# 03-8A34004_DPLL-1.net
KiCad netlist of a schematic drawn in Altium Designer
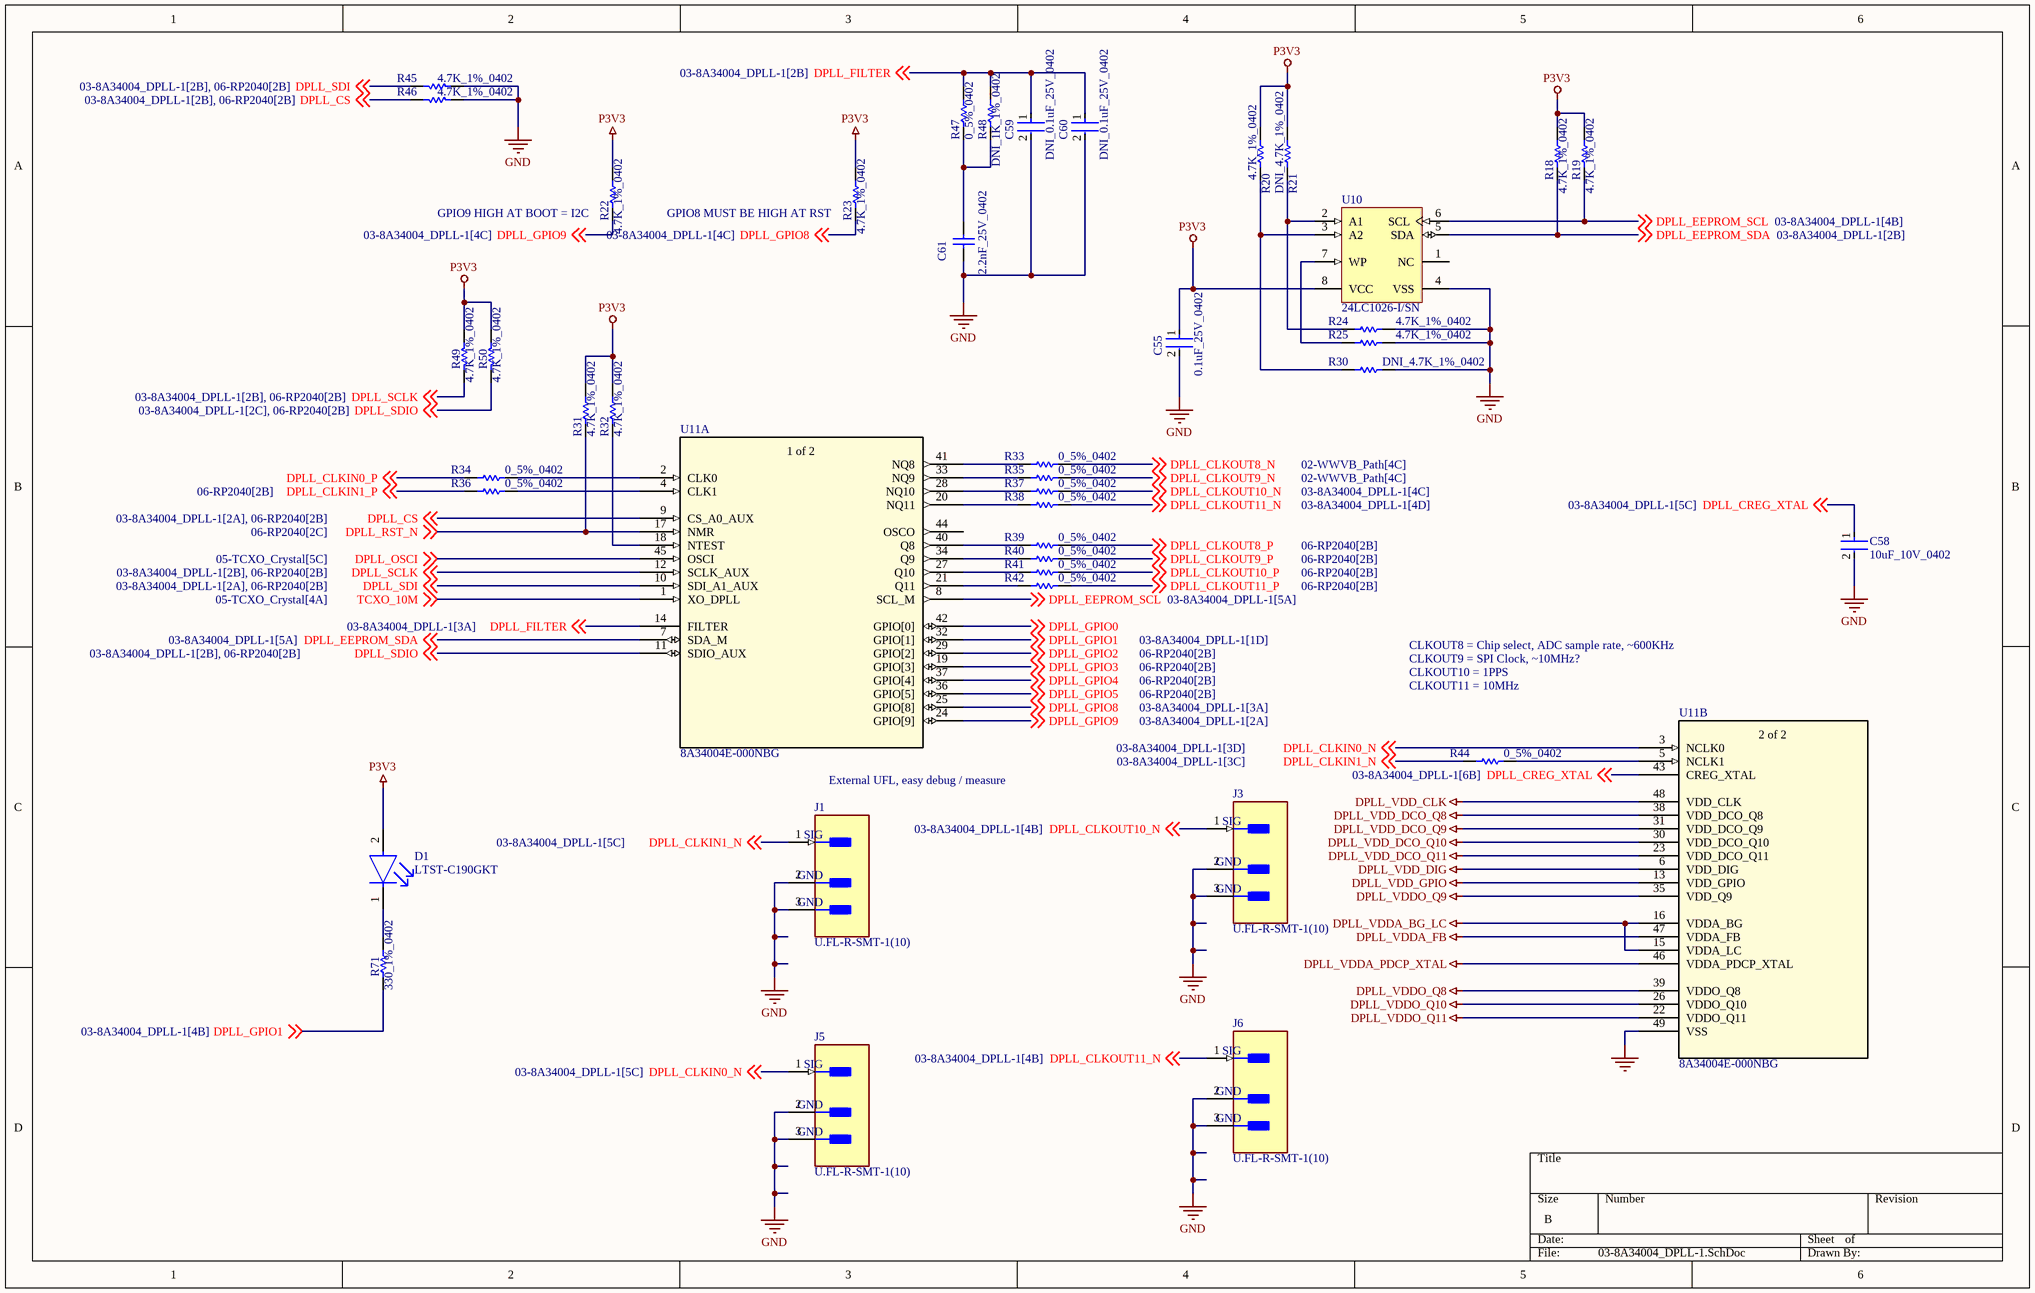
[diagram p0: 03-8A34004_DPLL-1.SchDoc]

(export (version "E")
  (design (tool "Eeschema 10.0.6"))
  (components
    (comp (ref "C55")
      (value "0.1uF_25V_0402")
      (footprint "FP-0402-L_1_0_1-W_0_5_0_1-IPC_C")
      (description "General Purpose Ceramic Capacitor, 0402, 100nF, 10%, X7R, 15%, 25V")
      (fields (field (name "VOLTAGE") "25V") (field (name "TOLERANCE") "10%"))
      (libsource (lib "Altium Content Vault") (part "b4654b650e69147ec39a6b967a45e02"))
    )
    (comp (ref "C58")
      (value "10uF_10V_0402")
      (footprint "FP-CL05A106MP5NUNC-MFG")
      (description "CAP CER 10UF 10V X5R 0402")
      (fields
        (field (name "OCTOPART") "https://octopart.com/cl05a106mp5nunc-samsung-22457395")
        (field (name "TOLERANCE") "20%")
      )
      (libsource (lib "Altium Content Vault") (part "b4654b650e69147ec39a6b967a45e02"))
    )
    (comp (ref "C59")
      (value "DNI_0.1uF_25V_0402")
      (footprint "FP-0402-L_1_0_1-W_0_5_0_1-IPC_C")
      (description "General Purpose Ceramic Capacitor, 0402, 100nF, 10%, X7R, 15%, 25V")
      (fields (field (name "VOLTAGE") "25V") (field (name "TOLERANCE") "10%"))
      (libsource (lib "Altium Content Vault") (part "b4654b650e69147ec39a6b967a45e02"))
    )
    (comp (ref "C60")
      (value "DNI_0.1uF_25V_0402")
      (footprint "FP-0402-L_1_0_1-W_0_5_0_1-IPC_C")
      (description "General Purpose Ceramic Capacitor, 0402, 100nF, 10%, X7R, 15%, 25V")
      (fields (field (name "VOLTAGE") "25V") (field (name "TOLERANCE") "10%"))
      (libsource (lib "Altium Content Vault") (part "b4654b650e69147ec39a6b967a45e02"))
    )
    (comp (ref "C61")
      (value "2.2nF_25V_0402")
      (footprint "CAPC1005X56X25LL10T15")
      (fields
        (field (name "MANUFACTURER") "AVX Interconnect / Elco")
        (field (name "PART NUMBER") "04025C222JAT2A")
      )
      (libsource (lib "Altium Content Vault") (part "CAP"))
    )
    (comp (ref "D1")
      (value "LTST-C190GKT")
      (footprint "FP-LTST-C190GKT-MFG")
      (description "LED GREEN CLEAR CHIP SMD")
      (fields (field (name "VOLTAGE") "2V"))
      (libsource (lib "Altium Content Vault") (part "8706943c75ba83719d021d2fdc84c58"))
    )
    (comp (ref "J1")
      (value "U.FL-R-SMT-1(10)")
      (footprint "FP-U_FL-R-SMT-1_10-MFG")
      (description "CONN U.FL RCPT STR 50 OHM SMD")
      (libsource (lib "Altium Content Vault") (part "7158abf7d987fa84906f6fb0d115710"))
    )
    (comp (ref "J3")
      (value "U.FL-R-SMT-1(10)")
      (footprint "FP-U_FL-R-SMT-1_10-MFG")
      (description "CONN U.FL RCPT STR 50 OHM SMD")
      (libsource (lib "Altium Content Vault") (part "7158abf7d987fa84906f6fb0d115710"))
    )
    (comp (ref "J5")
      (value "U.FL-R-SMT-1(10)")
      (footprint "FP-U_FL-R-SMT-1_10-MFG")
      (description "CONN U.FL RCPT STR 50 OHM SMD")
      (libsource (lib "Altium Content Vault") (part "7158abf7d987fa84906f6fb0d115710"))
    )
    (comp (ref "J6")
      (value "U.FL-R-SMT-1(10)")
      (footprint "FP-U_FL-R-SMT-1_10-MFG")
      (description "CONN U.FL RCPT STR 50 OHM SMD")
      (libsource (lib "Altium Content Vault") (part "7158abf7d987fa84906f6fb0d115710"))
    )
    (comp (ref "R18")
      (value "4.7K_1%_0402")
      (footprint "RESC1005X40X25NL10T10")
      (fields (field (name "MANUFACTURER") "Bourns") (field (name "PART NUMBER") "CR0402-FX-4701GLF"))
      (libsource (lib "Altium Content Vault") (part "RES"))
    )
    (comp (ref "R19")
      (value "4.7K_1%_0402")
      (footprint "RESC1005X40X25NL10T10")
      (fields (field (name "MANUFACTURER") "Bourns") (field (name "PART NUMBER") "CR0402-FX-4701GLF"))
      (libsource (lib "Altium Content Vault") (part "RES"))
    )
    (comp (ref "R20")
      (value "4.7K_1%_0402")
      (footprint "RESC1005X40X25NL10T10")
      (fields (field (name "MANUFACTURER") "Bourns") (field (name "PART NUMBER") "CR0402-FX-4701GLF"))
      (libsource (lib "Altium Content Vault") (part "RES"))
    )
    (comp (ref "R21")
      (value "DNI_4.7K_1%_0402")
      (footprint "RESC1005X40X25NL10T10")
      (fields (field (name "MANUFACTURER") "Bourns") (field (name "PART NUMBER") "CR0402-FX-4701GLF"))
      (libsource (lib "Altium Content Vault") (part "RES"))
    )
    (comp (ref "R22")
      (value "4.7K_1%_0402")
      (footprint "RESC1005X40X25NL10T10")
      (fields (field (name "MANUFACTURER") "Bourns") (field (name "PART NUMBER") "CR0402-FX-4701GLF"))
      (libsource (lib "Altium Content Vault") (part "RES"))
    )
    (comp (ref "R23")
      (value "4.7K_1%_0402")
      (footprint "RESC1005X40X25NL10T10")
      (fields (field (name "MANUFACTURER") "Bourns") (field (name "PART NUMBER") "CR0402-FX-4701GLF"))
      (libsource (lib "Altium Content Vault") (part "RES"))
    )
    (comp (ref "R24")
      (value "4.7K_1%_0402")
      (footprint "RESC1005X40X25NL10T10")
      (fields (field (name "MANUFACTURER") "Bourns") (field (name "PART NUMBER") "CR0402-FX-4701GLF"))
      (libsource (lib "Altium Content Vault") (part "RES"))
    )
    (comp (ref "R25")
      (value "4.7K_1%_0402")
      (footprint "RESC1005X40X25NL10T10")
      (fields (field (name "MANUFACTURER") "Bourns") (field (name "PART NUMBER") "CR0402-FX-4701GLF"))
      (libsource (lib "Altium Content Vault") (part "RES"))
    )
    (comp (ref "R30")
      (value "DNI_4.7K_1%_0402")
      (footprint "RESC1005X40X25NL10T10")
      (fields (field (name "MANUFACTURER") "Bourns") (field (name "PART NUMBER") "CR0402-FX-4701GLF"))
      (libsource (lib "Altium Content Vault") (part "RES"))
    )
    (comp (ref "R31")
      (value "4.7K_1%_0402")
      (footprint "RESC1005X40X25NL10T10")
      (fields (field (name "MANUFACTURER") "Bourns") (field (name "PART NUMBER") "CR0402-FX-4701GLF"))
      (libsource (lib "Altium Content Vault") (part "RES"))
    )
    (comp (ref "R32")
      (value "4.7K_1%_0402")
      (footprint "RESC1005X40X25NL10T10")
      (fields (field (name "MANUFACTURER") "Bourns") (field (name "PART NUMBER") "CR0402-FX-4701GLF"))
      (libsource (lib "Altium Content Vault") (part "RES"))
    )
    (comp (ref "R33")
      (value "0_5%_0402")
      (footprint "RESC1005X40X25NL05T10")
      (fields (field (name "MANUFACTURER") "Panasonic") (field (name "PART NUMBER") "ERJ-U020R00X"))
      (libsource (lib "Altium Content Vault") (part "RES"))
    )
    (comp (ref "R34")
      (value "0_5%_0402")
      (footprint "RESC1005X40X25NL05T10")
      (fields (field (name "MANUFACTURER") "Panasonic") (field (name "PART NUMBER") "ERJ-U020R00X"))
      (libsource (lib "Altium Content Vault") (part "RES"))
    )
    (comp (ref "R35")
      (value "0_5%_0402")
      (footprint "RESC1005X40X25NL05T10")
      (fields (field (name "MANUFACTURER") "Panasonic") (field (name "PART NUMBER") "ERJ-U020R00X"))
      (libsource (lib "Altium Content Vault") (part "RES"))
    )
    (comp (ref "R36")
      (value "0_5%_0402")
      (footprint "RESC1005X40X25NL05T10")
      (fields (field (name "MANUFACTURER") "Panasonic") (field (name "PART NUMBER") "ERJ-U020R00X"))
      (libsource (lib "Altium Content Vault") (part "RES"))
    )
    (comp (ref "R37")
      (value "0_5%_0402")
      (footprint "RESC1005X40X25NL05T10")
      (fields (field (name "MANUFACTURER") "Panasonic") (field (name "PART NUMBER") "ERJ-U020R00X"))
      (libsource (lib "Altium Content Vault") (part "RES"))
    )
    (comp (ref "R38")
      (value "0_5%_0402")
      (footprint "RESC1005X40X25NL05T10")
      (fields (field (name "MANUFACTURER") "Panasonic") (field (name "PART NUMBER") "ERJ-U020R00X"))
      (libsource (lib "Altium Content Vault") (part "RES"))
    )
    (comp (ref "R39")
      (value "0_5%_0402")
      (footprint "RESC1005X40X25NL05T10")
      (fields (field (name "MANUFACTURER") "Panasonic") (field (name "PART NUMBER") "ERJ-U020R00X"))
      (libsource (lib "Altium Content Vault") (part "RES"))
    )
    (comp (ref "R40")
      (value "0_5%_0402")
      (footprint "RESC1005X40X25NL05T10")
      (fields (field (name "MANUFACTURER") "Panasonic") (field (name "PART NUMBER") "ERJ-U020R00X"))
      (libsource (lib "Altium Content Vault") (part "RES"))
    )
    (comp (ref "R41")
      (value "0_5%_0402")
      (footprint "RESC1005X40X25NL05T10")
      (fields (field (name "MANUFACTURER") "Panasonic") (field (name "PART NUMBER") "ERJ-U020R00X"))
      (libsource (lib "Altium Content Vault") (part "RES"))
    )
    (comp (ref "R42")
      (value "0_5%_0402")
      (footprint "RESC1005X40X25NL05T10")
      (fields (field (name "MANUFACTURER") "Panasonic") (field (name "PART NUMBER") "ERJ-U020R00X"))
      (libsource (lib "Altium Content Vault") (part "RES"))
    )
    (comp (ref "R44")
      (value "0_5%_0402")
      (footprint "RESC1005X40X25NL05T10")
      (fields (field (name "MANUFACTURER") "Panasonic") (field (name "PART NUMBER") "ERJ-U020R00X"))
      (libsource (lib "Altium Content Vault") (part "RES"))
    )
    (comp (ref "R45")
      (value "4.7K_1%_0402")
      (footprint "RESC1005X40X25NL10T10")
      (fields (field (name "MANUFACTURER") "Bourns") (field (name "PART NUMBER") "CR0402-FX-4701GLF"))
      (libsource (lib "Altium Content Vault") (part "RES"))
    )
    (comp (ref "R46")
      (value "4.7K_1%_0402")
      (footprint "RESC1005X40X25NL10T10")
      (fields (field (name "MANUFACTURER") "Bourns") (field (name "PART NUMBER") "CR0402-FX-4701GLF"))
      (libsource (lib "Altium Content Vault") (part "RES"))
    )
    (comp (ref "R47")
      (value "0_5%_0402")
      (footprint "RESC1005X40X25LL10T10")
      (fields (field (name "MANUFACTURER") "KOA Speer") (field (name "PART NUMBER") "RK73Z1ETTP"))
      (libsource (lib "Altium Content Vault") (part "RES"))
    )
    (comp (ref "R48")
      (value "DNI_1K_1%_0402")
      (footprint "RESC1005X40X25NL05T05")
      (fields (field (name "MANUFACTURER") "Vishay Dale") (field (name "PART NUMBER") "CRCW04021K00FKTD"))
      (libsource (lib "Altium Content Vault") (part "RES"))
    )
    (comp (ref "R49")
      (value "4.7K_1%_0402")
      (footprint "RESC1005X40X25NL10T10")
      (fields (field (name "MANUFACTURER") "Bourns") (field (name "PART NUMBER") "CR0402-FX-4701GLF"))
      (libsource (lib "Altium Content Vault") (part "RES"))
    )
    (comp (ref "R50")
      (value "4.7K_1%_0402")
      (footprint "RESC1005X40X25NL10T10")
      (fields (field (name "MANUFACTURER") "Bourns") (field (name "PART NUMBER") "CR0402-FX-4701GLF"))
      (libsource (lib "Altium Content Vault") (part "RES"))
    )
    (comp (ref "R71")
      (value "330_1%_0402")
      (footprint "RESC1005X40X25NL10T10")
      (fields (field (name "MANUFACTURER") "Panasonic") (field (name "PART NUMBER") "ERA-2AED331X"))
      (libsource (lib "Altium Content Vault") (part "RES"))
    )
    (comp (ref "U10")
      (value "24LC1026-I/SN")
      (footprint "MCHP-SOIC-SN8_N")
      (description "1024K bits I2C™ Serial EEPROM, 2.5 to 5.5 V, 400 kHz, -40 to 85 degC, 8-pin SOIC (SN8), Tube")
      (fields (field (name "MANUFACTURER") "Microchip"))
      (libsource (lib "Altium Content Vault") (part "MCHP-24LC1026-SOIC-8"))
    )
    (comp (ref "U11")
      (value "8A34004E-000NBG")
      (footprint "NBG48P1_REN")
      (description "No Description Available")
      (libsource (lib "8A34004E-000NBG") (part "8A34004E-000NBG"))
    )
  )
  (nets
    (net (code "1") (name "DPLL_CLKIN0_N") (class "Default")
      (node (ref "J5") (pin "1") (pinfunction "SIG_1") (pintype "input"))
      (node (ref "U11") (pin "3") (pinfunction "NCLK0_3") (pintype "input"))
    )
    (net (code "2") (name "DPLL_CLKIN0_P") (class "Default")
      (node (ref "R34") (pin "1") (pinfunction "1_1") (pintype "passive"))
    )
    (net (code "3") (name "DPLL_CLKIN1_N") (class "Default")
      (node (ref "J1") (pin "1") (pinfunction "SIG_1") (pintype "input"))
      (node (ref "R44") (pin "1") (pinfunction "1_1") (pintype "passive"))
    )
    (net (code "4") (name "DPLL_CLKIN1_P") (class "Default")
      (node (ref "R36") (pin "1") (pinfunction "1_1") (pintype "passive"))
    )
    (net (code "5") (name "DPLL_CLKOUT8_N") (class "Default")
      (node (ref "R33") (pin "2") (pinfunction "2_2") (pintype "passive"))
    )
    (net (code "6") (name "DPLL_CLKOUT8_P") (class "Default")
      (node (ref "R39") (pin "2") (pinfunction "2_2") (pintype "passive"))
    )
    (net (code "7") (name "DPLL_CLKOUT9_N") (class "Default")
      (node (ref "R35") (pin "2") (pinfunction "2_2") (pintype "passive"))
    )
    (net (code "8") (name "DPLL_CLKOUT9_P") (class "Default")
      (node (ref "R40") (pin "2") (pinfunction "2_2") (pintype "passive"))
    )
    (net (code "9") (name "DPLL_CLKOUT10_N") (class "Default")
      (node (ref "J3") (pin "1") (pinfunction "SIG_1") (pintype "input"))
      (node (ref "R37") (pin "2") (pinfunction "2_2") (pintype "passive"))
    )
    (net (code "10") (name "DPLL_CLKOUT10_P") (class "Default")
      (node (ref "R41") (pin "2") (pinfunction "2_2") (pintype "passive"))
    )
    (net (code "11") (name "DPLL_CLKOUT11_N") (class "Default")
      (node (ref "J6") (pin "1") (pinfunction "SIG_1") (pintype "input"))
      (node (ref "R38") (pin "2") (pinfunction "2_2") (pintype "passive"))
    )
    (net (code "12") (name "DPLL_CLKOUT11_P") (class "Default")
      (node (ref "R42") (pin "2") (pinfunction "2_2") (pintype "passive"))
    )
    (net (code "13") (name "DPLL_CREG_XTAL") (class "Default")
      (node (ref "C58") (pin "1") (pinfunction "1_1") (pintype "passive"))
      (node (ref "U11") (pin "43") (pinfunction "CREG_XTAL_43") (pintype "power_in"))
    )
    (net (code "14") (name "DPLL_CS") (class "Default")
      (node (ref "R46") (pin "1") (pinfunction "1_1") (pintype "passive"))
      (node (ref "U11") (pin "9") (pinfunction "CS_A0_AUX_9") (pintype "input"))
    )
    (net (code "15") (name "DPLL_EEPROM_SCL") (class "Default")
      (node (ref "R19") (pin "2") (pinfunction "2_2") (pintype "passive"))
      (node (ref "U10") (pin "6") (pinfunction "SCL_6") (pintype "input"))
      (node (ref "U11") (pin "8") (pinfunction "SCL_M_8") (pintype "output"))
    )
    (net (code "16") (name "DPLL_EEPROM_SDA") (class "Default")
      (node (ref "R18") (pin "2") (pinfunction "2_2") (pintype "passive"))
      (node (ref "U10") (pin "5") (pinfunction "SDA_5") (pintype "bidirectional"))
      (node (ref "U11") (pin "7") (pinfunction "SDA_M_7") (pintype "bidirectional"))
    )
    (net (code "17") (name "DPLL_FILTER") (class "Default")
      (node (ref "C59") (pin "1") (pinfunction "1_1") (pintype "passive"))
      (node (ref "C60") (pin "1") (pinfunction "1_1") (pintype "passive"))
      (node (ref "R47") (pin "2") (pinfunction "2_2") (pintype "passive"))
      (node (ref "R48") (pin "2") (pinfunction "2_2") (pintype "passive"))
      (node (ref "U11") (pin "14") (pinfunction "FILTER_14") (pintype "passive"))
    )
    (net (code "18") (name "DPLL_GPIO0") (class "Default")
      (node (ref "U11") (pin "42") (pinfunction "GPIO[0]_42") (pintype "bidirectional"))
    )
    (net (code "19") (name "DPLL_GPIO1") (class "Default")
      (node (ref "R71") (pin "1") (pinfunction "1_1") (pintype "passive"))
      (node (ref "U11") (pin "32") (pinfunction "GPIO[1]_32") (pintype "bidirectional"))
    )
    (net (code "20") (name "DPLL_GPIO2") (class "Default")
      (node (ref "U11") (pin "29") (pinfunction "GPIO[2]_29") (pintype "bidirectional"))
    )
    (net (code "21") (name "DPLL_GPIO3") (class "Default")
      (node (ref "U11") (pin "19") (pinfunction "GPIO[3]_19") (pintype "bidirectional"))
    )
    (net (code "22") (name "DPLL_GPIO4") (class "Default")
      (node (ref "U11") (pin "37") (pinfunction "GPIO[4]_37") (pintype "bidirectional"))
    )
    (net (code "23") (name "DPLL_GPIO5") (class "Default")
      (node (ref "U11") (pin "36") (pinfunction "GPIO[5]_36") (pintype "bidirectional"))
    )
    (net (code "24") (name "DPLL_GPIO8") (class "Default")
      (node (ref "R23") (pin "2") (pinfunction "2_2") (pintype "passive"))
      (node (ref "U11") (pin "25") (pinfunction "GPIO[8]_25") (pintype "bidirectional"))
    )
    (net (code "25") (name "DPLL_GPIO9") (class "Default")
      (node (ref "R22") (pin "2") (pinfunction "2_2") (pintype "passive"))
      (node (ref "U11") (pin "24") (pinfunction "GPIO[9]_24") (pintype "bidirectional"))
    )
    (net (code "26") (name "DPLL_OSCI") (class "Default")
      (node (ref "U11") (pin "45") (pinfunction "OSCI_45") (pintype "input"))
    )
    (net (code "27") (name "DPLL_RST_N") (class "Default")
      (node (ref "R31") (pin "1") (pinfunction "1_1") (pintype "passive"))
      (node (ref "U11") (pin "17") (pinfunction "NMR_17") (pintype "input"))
    )
    (net (code "28") (name "DPLL_SCLK") (class "Default")
      (node (ref "R49") (pin "1") (pinfunction "1_1") (pintype "passive"))
      (node (ref "U11") (pin "12") (pinfunction "SCLK_AUX_12") (pintype "input"))
    )
    (net (code "29") (name "DPLL_SDI") (class "Default")
      (node (ref "R45") (pin "1") (pinfunction "1_1") (pintype "passive"))
      (node (ref "U11") (pin "10") (pinfunction "SDI_A1_AUX_10") (pintype "input"))
    )
    (net (code "30") (name "DPLL_SDIO") (class "Default")
      (node (ref "R50") (pin "1") (pinfunction "1_1") (pintype "passive"))
      (node (ref "U11") (pin "11") (pinfunction "SDIO_AUX_11") (pintype "bidirectional"))
    )
    (net (code "31") (name "DPLL_VDDA_BG_LC") (class "Default")
      (node (ref "U11") (pin "15") (pinfunction "VDDA_LC_15") (pintype "power_in"))
      (node (ref "U11") (pin "16") (pinfunction "VDDA_BG_16") (pintype "power_in"))
    )
    (net (code "32") (name "DPLL_VDDA_FB") (class "Default")
      (node (ref "U11") (pin "47") (pinfunction "VDDA_FB_47") (pintype "power_in"))
    )
    (net (code "33") (name "DPLL_VDDA_PDCP_XTAL") (class "Default")
      (node (ref "U11") (pin "46") (pinfunction "VDDA_PDCP_XTAL_46") (pintype "power_in"))
    )
    (net (code "34") (name "DPLL_VDDO_Q8") (class "Default")
      (node (ref "U11") (pin "39") (pinfunction "VDDO_Q8_39") (pintype "power_in"))
    )
    (net (code "35") (name "DPLL_VDDO_Q9") (class "Default")
      (node (ref "U11") (pin "35") (pinfunction "VDD_Q9_35") (pintype "power_in"))
    )
    (net (code "36") (name "DPLL_VDDO_Q10") (class "Default")
      (node (ref "U11") (pin "26") (pinfunction "VDDO_Q10_26") (pintype "power_in"))
    )
    (net (code "37") (name "DPLL_VDDO_Q11") (class "Default")
      (node (ref "U11") (pin "22") (pinfunction "VDDO_Q11_22") (pintype "power_in"))
    )
    (net (code "38") (name "DPLL_VDD_CLK") (class "Default")
      (node (ref "U11") (pin "48") (pinfunction "VDD_CLK_48") (pintype "power_in"))
    )
    (net (code "39") (name "DPLL_VDD_DCO_Q8") (class "Default")
      (node (ref "U11") (pin "38") (pinfunction "VDD_DCO_Q8_38") (pintype "power_in"))
    )
    (net (code "40") (name "DPLL_VDD_DCO_Q9") (class "Default")
      (node (ref "U11") (pin "31") (pinfunction "VDD_DCO_Q9_31") (pintype "power_in"))
    )
    (net (code "41") (name "DPLL_VDD_DCO_Q10") (class "Default")
      (node (ref "U11") (pin "30") (pinfunction "VDD_DCO_Q10_30") (pintype "power_in"))
    )
    (net (code "42") (name "DPLL_VDD_DCO_Q11") (class "Default")
      (node (ref "U11") (pin "23") (pinfunction "VDD_DCO_Q11_23") (pintype "power_in"))
    )
    (net (code "43") (name "DPLL_VDD_DIG") (class "Default")
      (node (ref "U11") (pin "6") (pinfunction "VDD_DIG_6") (pintype "power_in"))
    )
    (net (code "44") (name "DPLL_VDD_GPIO") (class "Default")
      (node (ref "U11") (pin "13") (pinfunction "VDD_GPIO_13") (pintype "power_in"))
    )
    (net (code "45") (name "GND") (class "Default")
      (node (ref "C55") (pin "2") (pinfunction "2_2") (pintype "passive"))
      (node (ref "C58") (pin "2") (pinfunction "2_2") (pintype "passive"))
      (node (ref "C59") (pin "2") (pinfunction "2_2") (pintype "passive"))
      (node (ref "C60") (pin "2") (pinfunction "2_2") (pintype "passive"))
      (node (ref "C61") (pin "1") (pinfunction "1_1") (pintype "passive"))
      (node (ref "J1") (pin "2") (pinfunction "GND_2") (pintype "power_in"))
      (node (ref "J1") (pin "3") (pinfunction "GND_3") (pintype "power_in"))
      (node (ref "J3") (pin "2") (pinfunction "GND_2") (pintype "power_in"))
      (node (ref "J3") (pin "3") (pinfunction "GND_3") (pintype "power_in"))
      (node (ref "J5") (pin "2") (pinfunction "GND_2") (pintype "power_in"))
      (node (ref "J5") (pin "3") (pinfunction "GND_3") (pintype "power_in"))
      (node (ref "J6") (pin "2") (pinfunction "GND_2") (pintype "power_in"))
      (node (ref "J6") (pin "3") (pinfunction "GND_3") (pintype "power_in"))
      (node (ref "R24") (pin "1") (pinfunction "1_1") (pintype "passive"))
      (node (ref "R25") (pin "1") (pinfunction "1_1") (pintype "passive"))
      (node (ref "R30") (pin "2") (pinfunction "2_2") (pintype "passive"))
      (node (ref "R45") (pin "2") (pinfunction "2_2") (pintype "passive"))
      (node (ref "R46") (pin "2") (pinfunction "2_2") (pintype "passive"))
      (node (ref "U10") (pin "4") (pinfunction "VSS_4") (pintype "power_in"))
      (node (ref "U11") (pin "49") (pinfunction "VSS_49") (pintype "power_in"))
    )
    (net (code "46") (name "Net-(C61-Pad2)") (class "Default")
      (node (ref "C61") (pin "2") (pinfunction "2_2") (pintype "passive"))
      (node (ref "R47") (pin "1") (pinfunction "1_1") (pintype "passive"))
      (node (ref "R48") (pin "1") (pinfunction "1_1") (pintype "passive"))
    )
    (net (code "47") (name "Net-(D1-C)") (class "Default")
      (node (ref "D1") (pin "1") (pinfunction "C_1") (pintype "passive"))
      (node (ref "R71") (pin "2") (pinfunction "2_2") (pintype "passive"))
    )
    (net (code "48") (name "Net-(U10-A1)") (class "Default")
      (node (ref "R21") (pin "1") (pinfunction "1_1") (pintype "passive"))
      (node (ref "R24") (pin "2") (pinfunction "2_2") (pintype "passive"))
      (node (ref "U10") (pin "2") (pinfunction "A1_2") (pintype "input"))
    )
    (net (code "49") (name "Net-(U10-A2)") (class "Default")
      (node (ref "R20") (pin "1") (pinfunction "1_1") (pintype "passive"))
      (node (ref "R30") (pin "1") (pinfunction "1_1") (pintype "passive"))
      (node (ref "U10") (pin "3") (pinfunction "A2_3") (pintype "input"))
    )
    (net (code "50") (name "Net-(U10-WP)") (class "Default")
      (node (ref "R25") (pin "2") (pinfunction "2_2") (pintype "passive"))
      (node (ref "U10") (pin "7") (pinfunction "WP_7") (pintype "input"))
    )
    (net (code "51") (name "Net-(U11A-CLK0)") (class "Default")
      (node (ref "R34") (pin "2") (pinfunction "2_2") (pintype "passive"))
      (node (ref "U11") (pin "2") (pinfunction "CLK0_2") (pintype "input"))
    )
    (net (code "52") (name "Net-(U11A-CLK1)") (class "Default")
      (node (ref "R36") (pin "2") (pinfunction "2_2") (pintype "passive"))
      (node (ref "U11") (pin "4") (pinfunction "CLK1_4") (pintype "input"))
    )
    (net (code "53") (name "Net-(U11A-NQ8)") (class "Default")
      (node (ref "R33") (pin "1") (pinfunction "1_1") (pintype "passive"))
      (node (ref "U11") (pin "41") (pinfunction "NQ8_41") (pintype "output"))
    )
    (net (code "54") (name "Net-(U11A-NQ9)") (class "Default")
      (node (ref "R35") (pin "1") (pinfunction "1_1") (pintype "passive"))
      (node (ref "U11") (pin "33") (pinfunction "NQ9_33") (pintype "output"))
    )
    (net (code "55") (name "Net-(U11A-NQ10)") (class "Default")
      (node (ref "R37") (pin "1") (pinfunction "1_1") (pintype "passive"))
      (node (ref "U11") (pin "28") (pinfunction "NQ10_28") (pintype "output"))
    )
    (net (code "56") (name "Net-(U11A-NQ11)") (class "Default")
      (node (ref "R38") (pin "1") (pinfunction "1_1") (pintype "passive"))
      (node (ref "U11") (pin "20") (pinfunction "NQ11_20") (pintype "output"))
    )
    (net (code "57") (name "Net-(U11A-NTEST)") (class "Default")
      (node (ref "R32") (pin "1") (pinfunction "1_1") (pintype "passive"))
      (node (ref "U11") (pin "18") (pinfunction "NTEST_18") (pintype "input"))
    )
    (net (code "58") (name "Net-(U11A-Q8)") (class "Default")
      (node (ref "R39") (pin "1") (pinfunction "1_1") (pintype "passive"))
      (node (ref "U11") (pin "40") (pinfunction "Q8_40") (pintype "output"))
    )
    (net (code "59") (name "Net-(U11A-Q9)") (class "Default")
      (node (ref "R40") (pin "1") (pinfunction "1_1") (pintype "passive"))
      (node (ref "U11") (pin "34") (pinfunction "Q9_34") (pintype "output"))
    )
    (net (code "60") (name "Net-(U11A-Q10)") (class "Default")
      (node (ref "R41") (pin "1") (pinfunction "1_1") (pintype "passive"))
      (node (ref "U11") (pin "27") (pinfunction "Q10_27") (pintype "output"))
    )
    (net (code "61") (name "Net-(U11A-Q11)") (class "Default")
      (node (ref "R42") (pin "1") (pinfunction "1_1") (pintype "passive"))
      (node (ref "U11") (pin "21") (pinfunction "Q11_21") (pintype "output"))
    )
    (net (code "62") (name "Net-(U11B-NCLK1)") (class "Default")
      (node (ref "R44") (pin "2") (pinfunction "2_2") (pintype "passive"))
      (node (ref "U11") (pin "5") (pinfunction "NCLK1_5") (pintype "input"))
    )
    (net (code "63") (name "P3V3") (class "Default")
      (node (ref "C55") (pin "1") (pinfunction "1_1") (pintype "passive"))
      (node (ref "D1") (pin "2") (pinfunction "A_2") (pintype "passive"))
      (node (ref "R18") (pin "1") (pinfunction "1_1") (pintype "passive"))
      (node (ref "R19") (pin "1") (pinfunction "1_1") (pintype "passive"))
      (node (ref "R20") (pin "2") (pinfunction "2_2") (pintype "passive"))
      (node (ref "R21") (pin "2") (pinfunction "2_2") (pintype "passive"))
      (node (ref "R22") (pin "1") (pinfunction "1_1") (pintype "passive"))
      (node (ref "R23") (pin "1") (pinfunction "1_1") (pintype "passive"))
      (node (ref "R31") (pin "2") (pinfunction "2_2") (pintype "passive"))
      (node (ref "R32") (pin "2") (pinfunction "2_2") (pintype "passive"))
      (node (ref "R49") (pin "2") (pinfunction "2_2") (pintype "passive"))
      (node (ref "R50") (pin "2") (pinfunction "2_2") (pintype "passive"))
      (node (ref "U10") (pin "8") (pinfunction "VCC_8") (pintype "power_in"))
    )
    (net (code "64") (name "TCXO_10M") (class "Default")
      (node (ref "U11") (pin "1") (pinfunction "XO_DPLL_1") (pintype "input"))
    )
    (net (code "65") (name "unconnected-(U10-NC-Pad1)") (class "Default")
      (node (ref "U10") (pin "1") (pinfunction "NC_1") (pintype "passive"))
    )
    (net (code "66") (name "unconnected-(U11A-OSCO-Pad44)") (class "Default")
      (node (ref "U11") (pin "44") (pinfunction "OSCO_44") (pintype "output"))
    )
  )
)
